# hexa_board.net
KiCad netlist of a schematic drawn in EAGLE
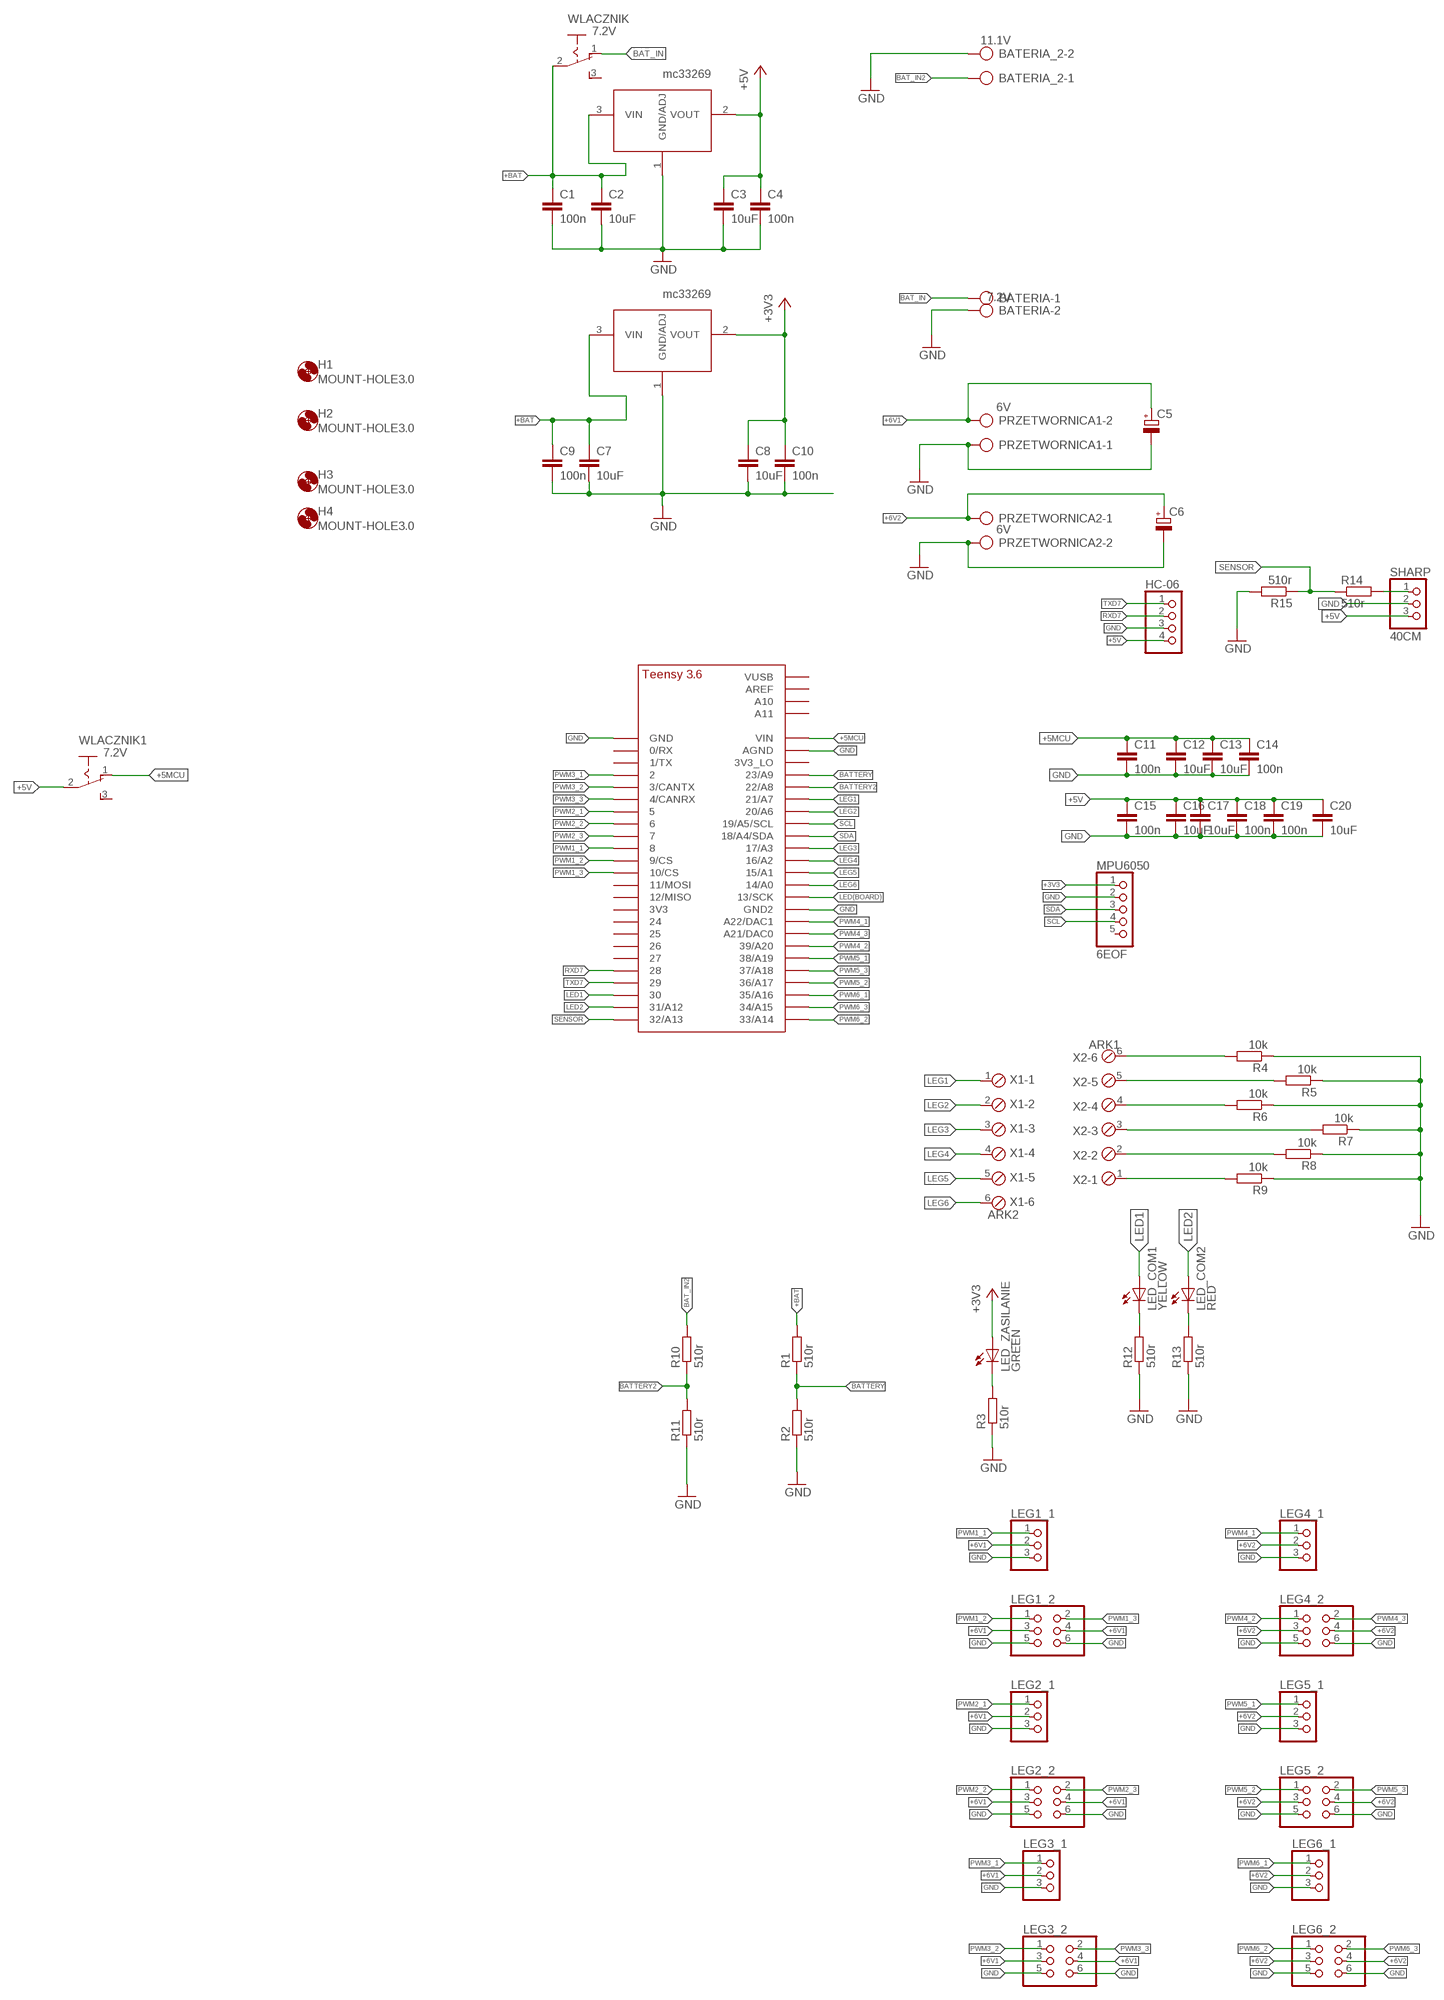
[diagram p0: schematic, sheet 1]

(export (version "E")
  (design (tool "Eeschema 10.0.6"))
  (components
    (comp (ref "3V")
      (value "MC33269")
      (footprint "eagle-import:TO220")
      (libsource (lib "eagle-import") (part "MC33269"))
    )
    (comp (ref "5V")
      (value "MC33269")
      (footprint "eagle-import:TO220")
      (libsource (lib "eagle-import") (part "MC33269"))
    )
    (comp (ref "BATERIA")
      (value "7.2V")
      (footprint "eagle-import:AK300_2")
      (libsource (lib "eagle-import") (part "AK300/2"))
    )
    (comp (ref "BATERIA_2")
      (value "11.1V")
      (footprint "eagle-import:AK300_2")
      (libsource (lib "eagle-import") (part "AK300/2"))
    )
    (comp (ref "C1")
      (value "100n")
      (footprint "eagle-import:C0805")
      (libsource (lib "eagle-import") (part "C-EUC0805"))
    )
    (comp (ref "C2")
      (value "10uF")
      (footprint "eagle-import:C1206")
      (libsource (lib "eagle-import") (part "C-EUC1206"))
    )
    (comp (ref "C3")
      (value "10uF")
      (footprint "eagle-import:C1206")
      (libsource (lib "eagle-import") (part "C-EUC1206"))
    )
    (comp (ref "C4")
      (value "100n")
      (footprint "eagle-import:C0805")
      (libsource (lib "eagle-import") (part "C-EUC0805"))
    )
    (comp (ref "C5")
      (value "CPOL-EU150CLZ-1014")
      (footprint "eagle-import:150CLZ-1014")
      (libsource (lib "eagle-import") (part "CPOL-EU150CLZ-1014"))
    )
    (comp (ref "C6")
      (value "CPOL-EU150CLZ-1014")
      (footprint "eagle-import:150CLZ-1014")
      (libsource (lib "eagle-import") (part "CPOL-EU150CLZ-1014"))
    )
    (comp (ref "C7")
      (value "10uF")
      (footprint "eagle-import:C1206")
      (libsource (lib "eagle-import") (part "C-EUC1206"))
    )
    (comp (ref "C8")
      (value "10uF")
      (footprint "eagle-import:C1206")
      (libsource (lib "eagle-import") (part "C-EUC1206"))
    )
    (comp (ref "C9")
      (value "100n")
      (footprint "eagle-import:C0805")
      (libsource (lib "eagle-import") (part "C-EUC0805"))
    )
    (comp (ref "C10")
      (value "100n")
      (footprint "eagle-import:C0805")
      (libsource (lib "eagle-import") (part "C-EUC0805"))
    )
    (comp (ref "C11")
      (value "100n")
      (footprint "eagle-import:C0805")
      (libsource (lib "eagle-import") (part "C-EUC0805"))
    )
    (comp (ref "C12")
      (value "10uF")
      (footprint "eagle-import:C1206")
      (libsource (lib "eagle-import") (part "C-EUC1206"))
    )
    (comp (ref "C13")
      (value "10uF")
      (footprint "eagle-import:C1206")
      (libsource (lib "eagle-import") (part "C-EUC1206"))
    )
    (comp (ref "C14")
      (value "100n")
      (footprint "eagle-import:C0805")
      (libsource (lib "eagle-import") (part "C-EUC0805"))
    )
    (comp (ref "C15")
      (value "100n")
      (footprint "eagle-import:C0805")
      (libsource (lib "eagle-import") (part "C-EUC0805"))
    )
    (comp (ref "C16")
      (value "10uF")
      (footprint "eagle-import:C1206")
      (libsource (lib "eagle-import") (part "C-EUC1206"))
    )
    (comp (ref "C17")
      (value "10uF")
      (footprint "eagle-import:C1206")
      (libsource (lib "eagle-import") (part "C-EUC1206"))
    )
    (comp (ref "C18")
      (value "100n")
      (footprint "eagle-import:C0805")
      (libsource (lib "eagle-import") (part "C-EUC0805"))
    )
    (comp (ref "C19")
      (value "100n")
      (footprint "eagle-import:C0805")
      (libsource (lib "eagle-import") (part "C-EUC0805"))
    )
    (comp (ref "C20")
      (value "10uF")
      (footprint "eagle-import:C1206")
      (libsource (lib "eagle-import") (part "C-EUC1206"))
    )
    (comp (ref "H1")
      (value "MOUNT-HOLE3.0")
      (footprint "eagle-import:3,0")
      (libsource (lib "eagle-import") (part "MOUNT-HOLE3.0"))
    )
    (comp (ref "H2")
      (value "MOUNT-HOLE3.0")
      (footprint "eagle-import:3,0")
      (libsource (lib "eagle-import") (part "MOUNT-HOLE3.0"))
    )
    (comp (ref "H3")
      (value "MOUNT-HOLE3.0")
      (footprint "eagle-import:3,0")
      (libsource (lib "eagle-import") (part "MOUNT-HOLE3.0"))
    )
    (comp (ref "H4")
      (value "MOUNT-HOLE3.0")
      (footprint "eagle-import:3,0")
      (libsource (lib "eagle-import") (part "MOUNT-HOLE3.0"))
    )
    (comp (ref "HC-06")
      (value "PINHD-1X4")
      (footprint "eagle-import:1X04")
      (libsource (lib "eagle-import") (part "PINHD-1X4"))
    )
    (comp (ref "LED_COM1")
      (value "YELLOW")
      (footprint "eagle-import:SML0805")
      (libsource (lib "eagle-import") (part "LEDSML0805"))
    )
    (comp (ref "LED_COM2")
      (value "RED")
      (footprint "eagle-import:SML0805")
      (libsource (lib "eagle-import") (part "LEDSML0805"))
    )
    (comp (ref "LED_ZASILANIE")
      (value "GREEN")
      (footprint "eagle-import:SML0805")
      (libsource (lib "eagle-import") (part "LEDSML0805"))
    )
    (comp (ref "LEG1_1")
      (value "PINHD-1X3")
      (footprint "eagle-import:1X03")
      (libsource (lib "eagle-import") (part "PINHD-1X3"))
    )
    (comp (ref "LEG1_2")
      (value "PINHD-2X3")
      (footprint "eagle-import:2X03")
      (libsource (lib "eagle-import") (part "PINHD-2X3"))
    )
    (comp (ref "LEG2_1")
      (value "PINHD-1X3")
      (footprint "eagle-import:1X03")
      (libsource (lib "eagle-import") (part "PINHD-1X3"))
    )
    (comp (ref "LEG2_2")
      (value "PINHD-2X3")
      (footprint "eagle-import:2X03")
      (libsource (lib "eagle-import") (part "PINHD-2X3"))
    )
    (comp (ref "LEG3_1")
      (value "PINHD-1X3")
      (footprint "eagle-import:1X03")
      (libsource (lib "eagle-import") (part "PINHD-1X3"))
    )
    (comp (ref "LEG3_2")
      (value "PINHD-2X3")
      (footprint "eagle-import:2X03")
      (libsource (lib "eagle-import") (part "PINHD-2X3"))
    )
    (comp (ref "LEG4_1")
      (value "PINHD-1X3")
      (footprint "eagle-import:1X03")
      (libsource (lib "eagle-import") (part "PINHD-1X3"))
    )
    (comp (ref "LEG4_2")
      (value "PINHD-2X3")
      (footprint "eagle-import:2X03")
      (libsource (lib "eagle-import") (part "PINHD-2X3"))
    )
    (comp (ref "LEG5_1")
      (value "PINHD-1X3")
      (footprint "eagle-import:1X03")
      (libsource (lib "eagle-import") (part "PINHD-1X3"))
    )
    (comp (ref "LEG5_2")
      (value "PINHD-2X3")
      (footprint "eagle-import:2X03")
      (libsource (lib "eagle-import") (part "PINHD-2X3"))
    )
    (comp (ref "LEG6_1")
      (value "PINHD-1X3")
      (footprint "eagle-import:1X03")
      (libsource (lib "eagle-import") (part "PINHD-1X3"))
    )
    (comp (ref "LEG6_2")
      (value "PINHD-2X3")
      (footprint "eagle-import:2X03")
      (libsource (lib "eagle-import") (part "PINHD-2X3"))
    )
    (comp (ref "MPU6050")
      (value "6EOF")
      (footprint "eagle-import:1X05")
      (libsource (lib "eagle-import") (part "PINHD-1X5"))
    )
    (comp (ref "PRZETWORNICA1")
      (value "6V")
      (footprint "eagle-import:AK300_2")
      (libsource (lib "eagle-import") (part "AK300/2"))
    )
    (comp (ref "PRZETWORNICA2")
      (value "6V")
      (footprint "eagle-import:AK300_2")
      (libsource (lib "eagle-import") (part "AK300/2"))
    )
    (comp (ref "R1")
      (value "510r")
      (footprint "eagle-import:R0805")
      (libsource (lib "eagle-import") (part "R-EU_R0805"))
    )
    (comp (ref "R2")
      (value "510r")
      (footprint "eagle-import:R0805")
      (libsource (lib "eagle-import") (part "R-EU_R0805"))
    )
    (comp (ref "R3")
      (value "510r")
      (footprint "eagle-import:R0805")
      (libsource (lib "eagle-import") (part "R-EU_R0805"))
    )
    (comp (ref "R4")
      (value "10k")
      (footprint "eagle-import:R0805")
      (libsource (lib "eagle-import") (part "R-EU_R0805"))
    )
    (comp (ref "R5")
      (value "10k")
      (footprint "eagle-import:R0805")
      (libsource (lib "eagle-import") (part "R-EU_R0805"))
    )
    (comp (ref "R6")
      (value "10k")
      (footprint "eagle-import:R0805")
      (libsource (lib "eagle-import") (part "R-EU_R0805"))
    )
    (comp (ref "R7")
      (value "10k")
      (footprint "eagle-import:R0805")
      (libsource (lib "eagle-import") (part "R-EU_R0805"))
    )
    (comp (ref "R8")
      (value "10k")
      (footprint "eagle-import:R0805")
      (libsource (lib "eagle-import") (part "R-EU_R0805"))
    )
    (comp (ref "R9")
      (value "10k")
      (footprint "eagle-import:R0805")
      (libsource (lib "eagle-import") (part "R-EU_R0805"))
    )
    (comp (ref "R10")
      (value "510r")
      (footprint "eagle-import:R0805")
      (libsource (lib "eagle-import") (part "R-EU_R0805"))
    )
    (comp (ref "R11")
      (value "510r")
      (footprint "eagle-import:R0805")
      (libsource (lib "eagle-import") (part "R-EU_R0805"))
    )
    (comp (ref "R12")
      (value "510r")
      (footprint "eagle-import:R0805")
      (libsource (lib "eagle-import") (part "R-EU_R0805"))
    )
    (comp (ref "R13")
      (value "510r")
      (footprint "eagle-import:R0805")
      (libsource (lib "eagle-import") (part "R-EU_R0805"))
    )
    (comp (ref "R14")
      (value "510r")
      (footprint "eagle-import:R0805")
      (libsource (lib "eagle-import") (part "R-EU_R0805"))
    )
    (comp (ref "R15")
      (value "510r")
      (footprint "eagle-import:R0805")
      (libsource (lib "eagle-import") (part "R-EU_R0805"))
    )
    (comp (ref "SHARP")
      (value "40CM")
      (footprint "eagle-import:1X03")
      (libsource (lib "eagle-import") (part "PINHD-1X3"))
    )
    (comp (ref "TEENSY41")
      (value "TEENSY_3.5/3.6_BASIC")
      (footprint "eagle-import:TEENSY_3.5_3.6_BASIC")
      (libsource (lib "eagle-import") (part "TEENSY_3.5/3.6_BASIC"))
    )
    (comp (ref "WLACZNIK")
      (value "7.2V")
      (footprint "eagle-import:255SB")
      (libsource (lib "eagle-import") (part "255SB"))
    )
    (comp (ref "WLACZNIK1")
      (value "7.2V")
      (footprint "eagle-import:255SB")
      (libsource (lib "eagle-import") (part "255SB"))
    )
    (comp (ref "X1")
      (value "ARK2")
      (footprint "eagle-import:6POL254")
      (libsource (lib "eagle-import") (part "MPT6"))
    )
    (comp (ref "X2")
      (value "ARK1")
      (footprint "eagle-import:6POL254")
      (libsource (lib "eagle-import") (part "MPT6"))
    )
  )
  (nets
    (net (code "1") (name "+3V3") (class "Default")
      (node (ref "3V") (pin "2") (pinfunction "VOUT_2") (pintype "bidirectional"))
      (node (ref "C10") (pin "1") (pinfunction "1_1") (pintype "passive"))
      (node (ref "C8") (pin "1") (pinfunction "1_1") (pintype "passive"))
      (node (ref "LED_ZASILANIE") (pin "A") (pinfunction "A_A") (pintype "passive"))
      (node (ref "MPU6050") (pin "1") (pinfunction "1_1") (pintype "passive"))
    )
    (net (code "2") (name "+5MCU") (class "Default")
      (node (ref "C11") (pin "1") (pinfunction "1_1") (pintype "passive"))
      (node (ref "C12") (pin "1") (pinfunction "1_1") (pintype "passive"))
      (node (ref "C13") (pin "1") (pinfunction "1_1") (pintype "passive"))
      (node (ref "C14") (pin "1") (pinfunction "1_1") (pintype "passive"))
      (node (ref "TEENSY41") (pin "VIN") (pinfunction "VIN_VIN") (pintype "bidirectional"))
      (node (ref "WLACZNIK1") (pin "1") (pinfunction "O_1") (pintype "passive"))
    )
    (net (code "3") (name "+5V") (class "Default")
      (node (ref "5V") (pin "2") (pinfunction "VOUT_2") (pintype "bidirectional"))
      (node (ref "C15") (pin "1") (pinfunction "1_1") (pintype "passive"))
      (node (ref "C16") (pin "1") (pinfunction "1_1") (pintype "passive"))
      (node (ref "C17") (pin "1") (pinfunction "1_1") (pintype "passive"))
      (node (ref "C18") (pin "1") (pinfunction "1_1") (pintype "passive"))
      (node (ref "C19") (pin "1") (pinfunction "1_1") (pintype "passive"))
      (node (ref "C20") (pin "1") (pinfunction "1_1") (pintype "passive"))
      (node (ref "C3") (pin "1") (pinfunction "1_1") (pintype "passive"))
      (node (ref "C4") (pin "1") (pinfunction "1_1") (pintype "passive"))
      (node (ref "HC-06") (pin "4") (pinfunction "4_4") (pintype "passive"))
      (node (ref "SHARP") (pin "3") (pinfunction "3_3") (pintype "passive"))
      (node (ref "WLACZNIK1") (pin "2") (pinfunction "P_2") (pintype "passive"))
    )
    (net (code "4") (name "+6V1") (class "Default")
      (node (ref "C5") (pin "+") (pinfunction "+_+") (pintype "passive"))
      (node (ref "LEG1_1") (pin "2") (pinfunction "2_2") (pintype "passive"))
      (node (ref "LEG1_2") (pin "3") (pinfunction "3_3") (pintype "passive"))
      (node (ref "LEG1_2") (pin "4") (pinfunction "4_4") (pintype "passive"))
      (node (ref "LEG2_1") (pin "2") (pinfunction "2_2") (pintype "passive"))
      (node (ref "LEG2_2") (pin "3") (pinfunction "3_3") (pintype "passive"))
      (node (ref "LEG2_2") (pin "4") (pinfunction "4_4") (pintype "passive"))
      (node (ref "LEG3_1") (pin "2") (pinfunction "2_2") (pintype "passive"))
      (node (ref "LEG3_2") (pin "3") (pinfunction "3_3") (pintype "passive"))
      (node (ref "LEG3_2") (pin "4") (pinfunction "4_4") (pintype "passive"))
      (node (ref "PRZETWORNICA1") (pin "2") (pinfunction "KL_2") (pintype "passive"))
    )
    (net (code "5") (name "+6V2") (class "Default")
      (node (ref "C6") (pin "+") (pinfunction "+_+") (pintype "passive"))
      (node (ref "LEG4_1") (pin "2") (pinfunction "2_2") (pintype "passive"))
      (node (ref "LEG4_2") (pin "3") (pinfunction "3_3") (pintype "passive"))
      (node (ref "LEG4_2") (pin "4") (pinfunction "4_4") (pintype "passive"))
      (node (ref "LEG5_1") (pin "2") (pinfunction "2_2") (pintype "passive"))
      (node (ref "LEG5_2") (pin "3") (pinfunction "3_3") (pintype "passive"))
      (node (ref "LEG5_2") (pin "4") (pinfunction "4_4") (pintype "passive"))
      (node (ref "LEG6_1") (pin "2") (pinfunction "2_2") (pintype "passive"))
      (node (ref "LEG6_2") (pin "3") (pinfunction "3_3") (pintype "passive"))
      (node (ref "LEG6_2") (pin "4") (pinfunction "4_4") (pintype "passive"))
      (node (ref "PRZETWORNICA2") (pin "1") (pinfunction "KL_1") (pintype "passive"))
    )
    (net (code "6") (name "+BAT") (class "Default")
      (node (ref "3V") (pin "3") (pinfunction "VIN_3") (pintype "bidirectional"))
      (node (ref "5V") (pin "3") (pinfunction "VIN_3") (pintype "bidirectional"))
      (node (ref "C1") (pin "1") (pinfunction "1_1") (pintype "passive"))
      (node (ref "C2") (pin "1") (pinfunction "1_1") (pintype "passive"))
      (node (ref "C7") (pin "1") (pinfunction "1_1") (pintype "passive"))
      (node (ref "C9") (pin "1") (pinfunction "1_1") (pintype "passive"))
      (node (ref "R1") (pin "2") (pinfunction "2_2") (pintype "passive"))
      (node (ref "WLACZNIK") (pin "2") (pinfunction "P_2") (pintype "passive"))
    )
    (net (code "7") (name "BATTERY") (class "Default")
      (node (ref "R1") (pin "1") (pinfunction "1_1") (pintype "passive"))
      (node (ref "R2") (pin "2") (pinfunction "2_2") (pintype "passive"))
      (node (ref "TEENSY41") (pin "23/A9") (pinfunction "23/A9_23/A9") (pintype "bidirectional"))
    )
    (net (code "8") (name "BATTERY2") (class "Default")
      (node (ref "R10") (pin "1") (pinfunction "1_1") (pintype "passive"))
      (node (ref "R11") (pin "2") (pinfunction "2_2") (pintype "passive"))
      (node (ref "TEENSY41") (pin "22/A8") (pinfunction "22/A8_22/A8") (pintype "bidirectional"))
    )
    (net (code "9") (name "BAT_IN") (class "Default")
      (node (ref "BATERIA") (pin "1") (pinfunction "KL_1") (pintype "passive"))
      (node (ref "WLACZNIK") (pin "1") (pinfunction "O_1") (pintype "passive"))
    )
    (net (code "10") (name "BAT_IN2") (class "Default")
      (node (ref "BATERIA_2") (pin "1") (pinfunction "KL_1") (pintype "passive"))
      (node (ref "R10") (pin "2") (pinfunction "2_2") (pintype "passive"))
    )
    (net (code "11") (name "GND") (class "Default")
      (node (ref "3V") (pin "1") (pinfunction "GND/ADJ_1") (pintype "bidirectional"))
      (node (ref "5V") (pin "1") (pinfunction "GND/ADJ_1") (pintype "bidirectional"))
      (node (ref "BATERIA") (pin "2") (pinfunction "KL_2") (pintype "passive"))
      (node (ref "BATERIA_2") (pin "2") (pinfunction "KL_2") (pintype "passive"))
      (node (ref "C1") (pin "2") (pinfunction "2_2") (pintype "passive"))
      (node (ref "C10") (pin "2") (pinfunction "2_2") (pintype "passive"))
      (node (ref "C11") (pin "2") (pinfunction "2_2") (pintype "passive"))
      (node (ref "C12") (pin "2") (pinfunction "2_2") (pintype "passive"))
      (node (ref "C13") (pin "2") (pinfunction "2_2") (pintype "passive"))
      (node (ref "C14") (pin "2") (pinfunction "2_2") (pintype "passive"))
      (node (ref "C15") (pin "2") (pinfunction "2_2") (pintype "passive"))
      (node (ref "C16") (pin "2") (pinfunction "2_2") (pintype "passive"))
      (node (ref "C17") (pin "2") (pinfunction "2_2") (pintype "passive"))
      (node (ref "C18") (pin "2") (pinfunction "2_2") (pintype "passive"))
      (node (ref "C19") (pin "2") (pinfunction "2_2") (pintype "passive"))
      (node (ref "C2") (pin "2") (pinfunction "2_2") (pintype "passive"))
      (node (ref "C20") (pin "2") (pinfunction "2_2") (pintype "passive"))
      (node (ref "C3") (pin "2") (pinfunction "2_2") (pintype "passive"))
      (node (ref "C4") (pin "2") (pinfunction "2_2") (pintype "passive"))
      (node (ref "C5") (pin "-") (pinfunction "-_-") (pintype "passive"))
      (node (ref "C6") (pin "-") (pinfunction "-_-") (pintype "passive"))
      (node (ref "C7") (pin "2") (pinfunction "2_2") (pintype "passive"))
      (node (ref "C8") (pin "2") (pinfunction "2_2") (pintype "passive"))
      (node (ref "C9") (pin "2") (pinfunction "2_2") (pintype "passive"))
      (node (ref "HC-06") (pin "3") (pinfunction "3_3") (pintype "passive"))
      (node (ref "LEG1_1") (pin "3") (pinfunction "3_3") (pintype "passive"))
      (node (ref "LEG1_2") (pin "5") (pinfunction "5_5") (pintype "passive"))
      (node (ref "LEG1_2") (pin "6") (pinfunction "6_6") (pintype "passive"))
      (node (ref "LEG2_1") (pin "3") (pinfunction "3_3") (pintype "passive"))
      (node (ref "LEG2_2") (pin "5") (pinfunction "5_5") (pintype "passive"))
      (node (ref "LEG2_2") (pin "6") (pinfunction "6_6") (pintype "passive"))
      (node (ref "LEG3_1") (pin "3") (pinfunction "3_3") (pintype "passive"))
      (node (ref "LEG3_2") (pin "5") (pinfunction "5_5") (pintype "passive"))
      (node (ref "LEG3_2") (pin "6") (pinfunction "6_6") (pintype "passive"))
      (node (ref "LEG4_1") (pin "3") (pinfunction "3_3") (pintype "passive"))
      (node (ref "LEG4_2") (pin "5") (pinfunction "5_5") (pintype "passive"))
      (node (ref "LEG4_2") (pin "6") (pinfunction "6_6") (pintype "passive"))
      (node (ref "LEG5_1") (pin "3") (pinfunction "3_3") (pintype "passive"))
      (node (ref "LEG5_2") (pin "5") (pinfunction "5_5") (pintype "passive"))
      (node (ref "LEG5_2") (pin "6") (pinfunction "6_6") (pintype "passive"))
      (node (ref "LEG6_1") (pin "3") (pinfunction "3_3") (pintype "passive"))
      (node (ref "LEG6_2") (pin "5") (pinfunction "5_5") (pintype "passive"))
      (node (ref "LEG6_2") (pin "6") (pinfunction "6_6") (pintype "passive"))
      (node (ref "MPU6050") (pin "2") (pinfunction "2_2") (pintype "passive"))
      (node (ref "PRZETWORNICA1") (pin "1") (pinfunction "KL_1") (pintype "passive"))
      (node (ref "PRZETWORNICA2") (pin "2") (pinfunction "KL_2") (pintype "passive"))
      (node (ref "R11") (pin "1") (pinfunction "1_1") (pintype "passive"))
      (node (ref "R12") (pin "1") (pinfunction "1_1") (pintype "passive"))
      (node (ref "R13") (pin "1") (pinfunction "1_1") (pintype "passive"))
      (node (ref "R15") (pin "2") (pinfunction "2_2") (pintype "passive"))
      (node (ref "R2") (pin "1") (pinfunction "1_1") (pintype "passive"))
      (node (ref "R3") (pin "1") (pinfunction "1_1") (pintype "passive"))
      (node (ref "R4") (pin "1") (pinfunction "1_1") (pintype "passive"))
      (node (ref "R5") (pin "1") (pinfunction "1_1") (pintype "passive"))
      (node (ref "R6") (pin "1") (pinfunction "1_1") (pintype "passive"))
      (node (ref "R7") (pin "1") (pinfunction "1_1") (pintype "passive"))
      (node (ref "R8") (pin "1") (pinfunction "1_1") (pintype "passive"))
      (node (ref "R9") (pin "1") (pinfunction "1_1") (pintype "passive"))
      (node (ref "SHARP") (pin "2") (pinfunction "2_2") (pintype "passive"))
      (node (ref "TEENSY41") (pin "AGND") (pinfunction "AGND_AGND") (pintype "bidirectional"))
      (node (ref "TEENSY41") (pin "GND") (pinfunction "GND_GND") (pintype "bidirectional"))
      (node (ref "TEENSY41") (pin "GND2") (pinfunction "GND2_GND2") (pintype "bidirectional"))
    )
    (net (code "12") (name "LED(BOARD)") (class "Default")
      (node (ref "TEENSY41") (pin "13/SCK") (pinfunction "13/SCK_13/SCK") (pintype "bidirectional"))
    )
    (net (code "13") (name "LED1") (class "Default")
      (node (ref "LED_COM1") (pin "A") (pinfunction "A_A") (pintype "passive"))
      (node (ref "TEENSY41") (pin "30") (pinfunction "30_30") (pintype "bidirectional"))
    )
    (net (code "14") (name "LED2") (class "Default")
      (node (ref "LED_COM2") (pin "A") (pinfunction "A_A") (pintype "passive"))
      (node (ref "TEENSY41") (pin "31/A12") (pinfunction "31/A12_31/A12") (pintype "bidirectional"))
    )
    (net (code "15") (name "LEG1") (class "Default")
      (node (ref "TEENSY41") (pin "21/A7") (pinfunction "21/A7_21/A7") (pintype "bidirectional"))
      (node (ref "X1") (pin "1") (pinfunction "1_1") (pintype "passive"))
    )
    (net (code "16") (name "LEG2") (class "Default")
      (node (ref "TEENSY41") (pin "20/A6") (pinfunction "20/A6_20/A6") (pintype "bidirectional"))
      (node (ref "X1") (pin "2") (pinfunction "1_2") (pintype "passive"))
    )
    (net (code "17") (name "LEG3") (class "Default")
      (node (ref "TEENSY41") (pin "17/A3") (pinfunction "17/A3_17/A3") (pintype "bidirectional"))
      (node (ref "X1") (pin "3") (pinfunction "1_3") (pintype "passive"))
    )
    (net (code "18") (name "LEG4") (class "Default")
      (node (ref "TEENSY41") (pin "16/A2") (pinfunction "16/A2_16/A2") (pintype "bidirectional"))
      (node (ref "X1") (pin "4") (pinfunction "1_4") (pintype "passive"))
    )
    (net (code "19") (name "LEG5") (class "Default")
      (node (ref "TEENSY41") (pin "15/A1") (pinfunction "15/A1_15/A1") (pintype "bidirectional"))
      (node (ref "X1") (pin "5") (pinfunction "1_5") (pintype "passive"))
    )
    (net (code "20") (name "LEG6") (class "Default")
      (node (ref "TEENSY41") (pin "14/A0") (pinfunction "14/A0_14/A0") (pintype "bidirectional"))
      (node (ref "X1") (pin "6") (pinfunction "1_6") (pintype "passive"))
    )
    (net (code "21") (name "Net-(LED_COM1-PadC)") (class "Default")
      (node (ref "LED_COM1") (pin "C") (pinfunction "C_C") (pintype "passive"))
      (node (ref "R12") (pin "2") (pinfunction "2_2") (pintype "passive"))
    )
    (net (code "22") (name "Net-(LED_COM2-PadC)") (class "Default")
      (node (ref "LED_COM2") (pin "C") (pinfunction "C_C") (pintype "passive"))
      (node (ref "R13") (pin "2") (pinfunction "2_2") (pintype "passive"))
    )
    (net (code "23") (name "Net-(LED_ZASILANIE-PadC)") (class "Default")
      (node (ref "LED_ZASILANIE") (pin "C") (pinfunction "C_C") (pintype "passive"))
      (node (ref "R3") (pin "2") (pinfunction "2_2") (pintype "passive"))
    )
    (net (code "24") (name "Net-(R9-Pad2)") (class "Default")
      (node (ref "R9") (pin "2") (pinfunction "2_2") (pintype "passive"))
      (node (ref "X2") (pin "1") (pinfunction "1_1") (pintype "passive"))
    )
    (net (code "25") (name "Net-(R14-Pad2)") (class "Default")
      (node (ref "R14") (pin "2") (pinfunction "2_2") (pintype "passive"))
      (node (ref "SHARP") (pin "1") (pinfunction "1_1") (pintype "passive"))
    )
    (net (code "26") (name "Net-(X2B-1)") (class "Default")
      (node (ref "R8") (pin "2") (pinfunction "2_2") (pintype "passive"))
      (node (ref "X2") (pin "2") (pinfunction "1_2") (pintype "passive"))
    )
    (net (code "27") (name "Net-(X2C-1)") (class "Default")
      (node (ref "R7") (pin "2") (pinfunction "2_2") (pintype "passive"))
      (node (ref "X2") (pin "3") (pinfunction "1_3") (pintype "passive"))
    )
    (net (code "28") (name "Net-(X2D-1)") (class "Default")
      (node (ref "R6") (pin "2") (pinfunction "2_2") (pintype "passive"))
      (node (ref "X2") (pin "4") (pinfunction "1_4") (pintype "passive"))
    )
    (net (code "29") (name "Net-(X2E-1)") (class "Default")
      (node (ref "R5") (pin "2") (pinfunction "2_2") (pintype "passive"))
      (node (ref "X2") (pin "5") (pinfunction "1_5") (pintype "passive"))
    )
    (net (code "30") (name "Net-(X2F-1)") (class "Default")
      (node (ref "R4") (pin "2") (pinfunction "2_2") (pintype "passive"))
      (node (ref "X2") (pin "6") (pinfunction "1_6") (pintype "passive"))
    )
    (net (code "31") (name "PWM1_1") (class "Default")
      (node (ref "LEG1_1") (pin "1") (pinfunction "1_1") (pintype "passive"))
      (node (ref "TEENSY41") (pin "8") (pinfunction "8_8") (pintype "bidirectional"))
    )
    (net (code "32") (name "PWM1_2") (class "Default")
      (node (ref "LEG1_2") (pin "1") (pinfunction "1_1") (pintype "passive"))
      (node (ref "TEENSY41") (pin "9/CS") (pinfunction "9/CS_9/CS") (pintype "bidirectional"))
    )
    (net (code "33") (name "PWM1_3") (class "Default")
      (node (ref "LEG1_2") (pin "2") (pinfunction "2_2") (pintype "passive"))
      (node (ref "TEENSY41") (pin "10/CS") (pinfunction "10/CS_10/CS") (pintype "bidirectional"))
    )
    (net (code "34") (name "PWM2_1") (class "Default")
      (node (ref "LEG2_1") (pin "1") (pinfunction "1_1") (pintype "passive"))
      (node (ref "TEENSY41") (pin "5") (pinfunction "5_5") (pintype "bidirectional"))
    )
    (net (code "35") (name "PWM2_2") (class "Default")
      (node (ref "LEG2_2") (pin "1") (pinfunction "1_1") (pintype "passive"))
      (node (ref "TEENSY41") (pin "6") (pinfunction "6_6") (pintype "bidirectional"))
    )
    (net (code "36") (name "PWM2_3") (class "Default")
      (node (ref "LEG2_2") (pin "2") (pinfunction "2_2") (pintype "passive"))
      (node (ref "TEENSY41") (pin "7") (pinfunction "7_7") (pintype "bidirectional"))
    )
    (net (code "37") (name "PWM3_1") (class "Default")
      (node (ref "LEG3_1") (pin "1") (pinfunction "1_1") (pintype "passive"))
      (node (ref "TEENSY41") (pin "2") (pinfunction "2_2") (pintype "bidirectional"))
    )
    (net (code "38") (name "PWM3_2") (class "Default")
      (node (ref "LEG3_2") (pin "1") (pinfunction "1_1") (pintype "passive"))
      (node (ref "TEENSY41") (pin "3/CANTX") (pinfunction "3/CANTX_3/CANTX") (pintype "bidirectional"))
    )
    (net (code "39") (name "PWM3_3") (class "Default")
      (node (ref "LEG3_2") (pin "2") (pinfunction "2_2") (pintype "passive"))
      (node (ref "TEENSY41") (pin "4/CANRX") (pinfunction "4/CANRX_4/CANRX") (pintype "bidirectional"))
    )
    (net (code "40") (name "PWM4_1") (class "Default")
      (node (ref "LEG4_1") (pin "1") (pinfunction "1_1") (pintype "passive"))
      (node (ref "TEENSY41") (pin "A22/DAC1") (pinfunction "A22/DAC1_A22/DAC1") (pintype "bidirectional"))
    )
    (net (code "41") (name "PWM4_2") (class "Default")
      (node (ref "LEG4_2") (pin "1") (pinfunction "1_1") (pintype "passive"))
      (node (ref "TEENSY41") (pin "39/A20") (pinfunction "39/A20_39/A20") (pintype "bidirectional"))
    )
    (net (code "42") (name "PWM4_3") (class "Default")
      (node (ref "LEG4_2") (pin "2") (pinfunction "2_2") (pintype "passive"))
      (node (ref "TEENSY41") (pin "21/DAC0") (pinfunction "A21/DAC0_21/DAC0") (pintype "bidirectional"))
    )
    (net (code "43") (name "PWM5_1") (class "Default")
      (node (ref "LEG5_1") (pin "1") (pinfunction "1_1") (pintype "passive"))
      (node (ref "TEENSY41") (pin "38/A19") (pinfunction "38/A19_38/A19") (pintype "bidirectional"))
    )
    (net (code "44") (name "PWM5_2") (class "Default")
      (node (ref "LEG5_2") (pin "1") (pinfunction "1_1") (pintype "passive"))
      (node (ref "TEENSY41") (pin "36/A17") (pinfunction "36/A17_36/A17") (pintype "bidirectional"))
    )
    (net (code "45") (name "PWM5_3") (class "Default")
      (node (ref "LEG5_2") (pin "2") (pinfunction "2_2") (pintype "passive"))
      (node (ref "TEENSY41") (pin "37/A18") (pinfunction "37/A18_37/A18") (pintype "bidirectional"))
    )
    (net (code "46") (name "PWM6_1") (class "Default")
      (node (ref "LEG6_1") (pin "1") (pinfunction "1_1") (pintype "passive"))
      (node (ref "TEENSY41") (pin "35/A16") (pinfunction "35/A16_35/A16") (pintype "bidirectional"))
    )
    (net (code "47") (name "PWM6_2") (class "Default")
      (node (ref "LEG6_2") (pin "1") (pinfunction "1_1") (pintype "passive"))
      (node (ref "TEENSY41") (pin "33/A14") (pinfunction "33/A14_33/A14") (pintype "bidirectional"))
    )
    (net (code "48") (name "PWM6_3") (class "Default")
      (node (ref "LEG6_2") (pin "2") (pinfunction "2_2") (pintype "passive"))
      (node (ref "TEENSY41") (pin "34/A15") (pinfunction "34/A15_34/A15") (pintype "bidirectional"))
    )
    (net (code "49") (name "RXD7") (class "Default")
      (node (ref "HC-06") (pin "2") (pinfunction "2_2") (pintype "passive"))
      (node (ref "TEENSY41") (pin "28") (pinfunction "28_28") (pintype "bidirectional"))
    )
    (net (code "50") (name "SCL") (class "Default")
      (node (ref "MPU6050") (pin "4") (pinfunction "4_4") (pintype "passive"))
      (node (ref "TEENSY41") (pin "19/A5/SCL") (pinfunction "19/A5/SCL_19/A5/SCL") (pintype "bidirectional"))
    )
    (net (code "51") (name "SDA") (class "Default")
      (node (ref "MPU6050") (pin "3") (pinfunction "3_3") (pintype "passive"))
      (node (ref "TEENSY41") (pin "18/A4/SDA") (pinfunction "18/A4/SDA_18/A4/SDA") (pintype "bidirectional"))
    )
    (net (code "52") (name "SENSOR") (class "Default")
      (node (ref "R14") (pin "1") (pinfunction "1_1") (pintype "passive"))
      (node (ref "R15") (pin "1") (pinfunction "1_1") (pintype "passive"))
      (node (ref "TEENSY41") (pin "32/A13") (pinfunction "32/A13_32/A13") (pintype "bidirectional"))
    )
    (net (code "53") (name "TXD7") (class "Default")
      (node (ref "HC-06") (pin "1") (pinfunction "1_1") (pintype "passive"))
      (node (ref "TEENSY41") (pin "29") (pinfunction "29_29") (pintype "bidirectional"))
    )
    (net (code "54") (name "unconnected-(MPU6050-Pad5)") (class "Default")
      (node (ref "MPU6050") (pin "5") (pinfunction "5_5") (pintype "passive"))
    )
    (net (code "55") (name "unconnected-(TEENSY41-Pad0{slash}RX)") (class "Default")
      (node (ref "TEENSY41") (pin "0/RX") (pinfunction "0/RX_0/RX") (pintype "bidirectional"))
    )
    (net (code "56") (name "unconnected-(TEENSY41-Pad1{slash}TX)") (class "Default")
      (node (ref "TEENSY41") (pin "1/TX") (pinfunction "1/TX_1/TX") (pintype "bidirectional"))
    )
    (net (code "57") (name "unconnected-(TEENSY41-Pad3V3)") (class "Default")
      (node (ref "TEENSY41") (pin "3V3") (pinfunction "3V3_3V3") (pintype "bidirectional"))
    )
    (net (code "58") (name "unconnected-(TEENSY41-Pad3V3_LO)") (class "Default")
      (node (ref "TEENSY41") (pin "3V3_LO") (pinfunction "3V3_LO_3V3_LO") (pintype "bidirectional"))
    )
    (net (code "59") (name "unconnected-(TEENSY41-Pad11{slash}MOSI)") (class "Default")
      (node (ref "TEENSY41") (pin "11/MOSI") (pinfunction "11/MOSI_11/MOSI") (pintype "bidirectional"))
    )
    (net (code "60") (name "unconnected-(TEENSY41-Pad12{slash}MISO)") (class "Default")
      (node (ref "TEENSY41") (pin "12/MISO") (pinfunction "12/MISO_12/MISO") (pintype "bidirectional"))
    )
    (net (code "61") (name "unconnected-(TEENSY41-Pad24)") (class "Default")
      (node (ref "TEENSY41") (pin "24") (pinfunction "24_24") (pintype "bidirectional"))
    )
    (net (code "62") (name "unconnected-(TEENSY41-Pad25)") (class "Default")
      (node (ref "TEENSY41") (pin "25") (pinfunction "25_25") (pintype "bidirectional"))
    )
    (net (code "63") (name "unconnected-(TEENSY41-Pad26)") (class "Default")
      (node (ref "TEENSY41") (pin "26") (pinfunction "26_26") (pintype "bidirectional"))
    )
    (net (code "64") (name "unconnected-(TEENSY41-Pad27)") (class "Default")
      (node (ref "TEENSY41") (pin "27") (pinfunction "27_27") (pintype "bidirectional"))
    )
    (net (code "65") (name "unconnected-(TEENSY41-PadA10)") (class "Default")
      (node (ref "TEENSY41") (pin "A10") (pinfunction "A10_A10") (pintype "bidirectional"))
    )
    (net (code "66") (name "unconnected-(TEENSY41-PadA11)") (class "Default")
      (node (ref "TEENSY41") (pin "A11") (pinfunction "A11_A11") (pintype "bidirectional"))
    )
    (net (code "67") (name "unconnected-(TEENSY41-PadAREF)") (class "Default")
      (node (ref "TEENSY41") (pin "AREF") (pinfunction "AREF_AREF") (pintype "bidirectional"))
    )
    (net (code "68") (name "unconnected-(TEENSY41-PadVUSB)") (class "Default")
      (node (ref "TEENSY41") (pin "VUSB") (pinfunction "VUSB_VUSB") (pintype "bidirectional"))
    )
    (net (code "69") (name "unconnected-(WLACZNIK-S-Pad3)") (class "Default")
      (node (ref "WLACZNIK") (pin "3") (pinfunction "S_3") (pintype "passive"))
    )
    (net (code "70") (name "unconnected-(WLACZNIK1-S-Pad3)") (class "Default")
      (node (ref "WLACZNIK1") (pin "3") (pinfunction "S_3") (pintype "passive"))
    )
  )
)
